# SCH_7segment.net
KiCad netlist of a schematic drawn in EasyEDA
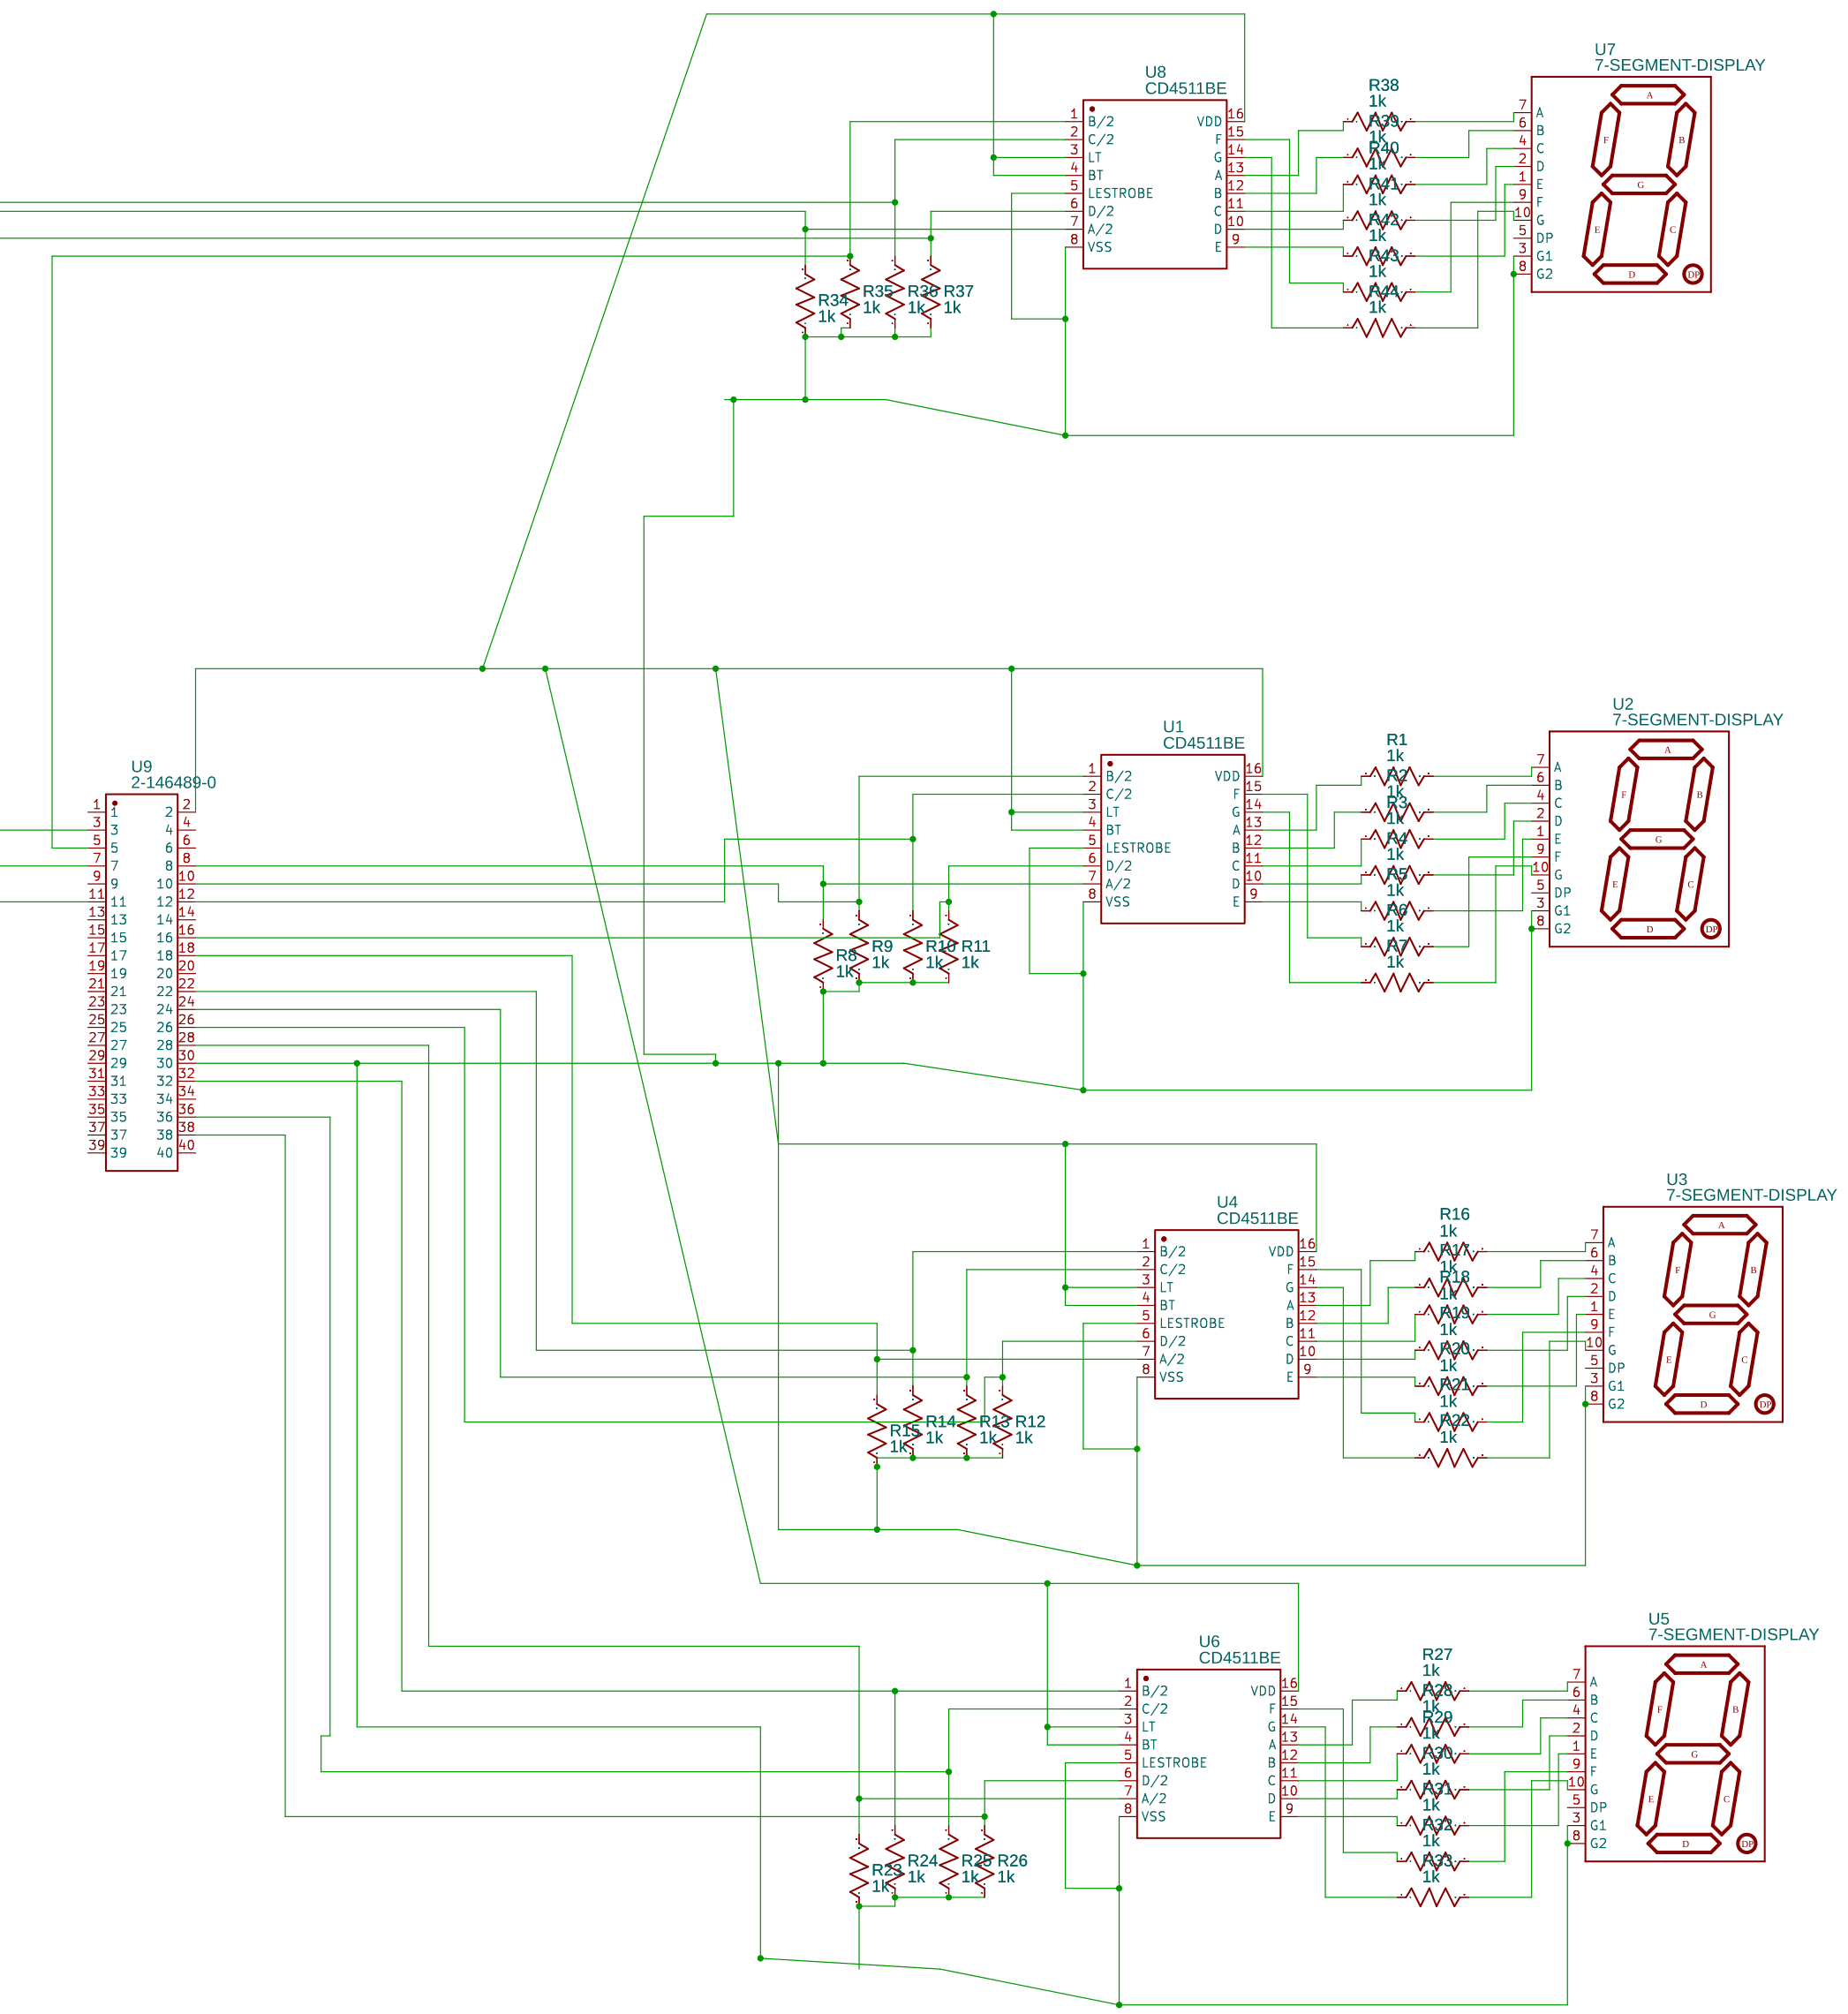
[diagram p0: schematic sheet]

(export (version "E")
  (design (tool "Eeschema 10.0.6"))
  (components
    (comp (ref "R1") (value "1k") (libsource (lib "") (part "R_AXIAL-0.4_US")))
    (comp (ref "R2") (value "1k") (libsource (lib "") (part "R_AXIAL-0.4_US")))
    (comp (ref "R3") (value "1k") (libsource (lib "") (part "R_AXIAL-0.4_US")))
    (comp (ref "R4") (value "1k") (libsource (lib "") (part "R_AXIAL-0.4_US")))
    (comp (ref "R5") (value "1k") (libsource (lib "") (part "R_AXIAL-0.4_US")))
    (comp (ref "R6") (value "1k") (libsource (lib "") (part "R_AXIAL-0.4_US")))
    (comp (ref "R7") (value "1k") (libsource (lib "") (part "R_AXIAL-0.4_US")))
    (comp (ref "R8") (value "1k") (libsource (lib "") (part "R_AXIAL-0.4_US_1")))
    (comp (ref "R9") (value "1k") (libsource (lib "") (part "R_AXIAL-0.4_US_1")))
    (comp (ref "R10") (value "1k") (libsource (lib "") (part "R_AXIAL-0.4_US_1")))
    (comp (ref "R11") (value "1k") (libsource (lib "") (part "R_AXIAL-0.4_US_1")))
    (comp (ref "R12") (value "1k") (libsource (lib "") (part "R_AXIAL-0.4_US_1")))
    (comp (ref "R13") (value "1k") (libsource (lib "") (part "R_AXIAL-0.4_US_1")))
    (comp (ref "R14") (value "1k") (libsource (lib "") (part "R_AXIAL-0.4_US_1")))
    (comp (ref "R15") (value "1k") (libsource (lib "") (part "R_AXIAL-0.4_US_1")))
    (comp (ref "R16") (value "1k") (libsource (lib "") (part "R_AXIAL-0.4_US")))
    (comp (ref "R17") (value "1k") (libsource (lib "") (part "R_AXIAL-0.4_US")))
    (comp (ref "R18") (value "1k") (libsource (lib "") (part "R_AXIAL-0.4_US")))
    (comp (ref "R19") (value "1k") (libsource (lib "") (part "R_AXIAL-0.4_US")))
    (comp (ref "R20") (value "1k") (libsource (lib "") (part "R_AXIAL-0.4_US")))
    (comp (ref "R21") (value "1k") (libsource (lib "") (part "R_AXIAL-0.4_US")))
    (comp (ref "R22") (value "1k") (libsource (lib "") (part "R_AXIAL-0.4_US")))
    (comp (ref "R23") (value "1k") (libsource (lib "") (part "R_AXIAL-0.4_US_1")))
    (comp (ref "R24") (value "1k") (libsource (lib "") (part "R_AXIAL-0.4_US_1")))
    (comp (ref "R25") (value "1k") (libsource (lib "") (part "R_AXIAL-0.4_US_1")))
    (comp (ref "R26") (value "1k") (libsource (lib "") (part "R_AXIAL-0.4_US_1")))
    (comp (ref "R27") (value "1k") (libsource (lib "") (part "R_AXIAL-0.4_US")))
    (comp (ref "R28") (value "1k") (libsource (lib "") (part "R_AXIAL-0.4_US")))
    (comp (ref "R29") (value "1k") (libsource (lib "") (part "R_AXIAL-0.4_US")))
    (comp (ref "R30") (value "1k") (libsource (lib "") (part "R_AXIAL-0.4_US")))
    (comp (ref "R31") (value "1k") (libsource (lib "") (part "R_AXIAL-0.4_US")))
    (comp (ref "R32") (value "1k") (libsource (lib "") (part "R_AXIAL-0.4_US")))
    (comp (ref "R33") (value "1k") (libsource (lib "") (part "R_AXIAL-0.4_US")))
    (comp (ref "R34") (value "1k") (libsource (lib "") (part "R_AXIAL-0.4_US_1")))
    (comp (ref "R35") (value "1k") (libsource (lib "") (part "R_AXIAL-0.4_US_1")))
    (comp (ref "R36") (value "1k") (libsource (lib "") (part "R_AXIAL-0.4_US_1")))
    (comp (ref "R37") (value "1k") (libsource (lib "") (part "R_AXIAL-0.4_US_1")))
    (comp (ref "R38") (value "1k") (libsource (lib "") (part "R_AXIAL-0.4_US")))
    (comp (ref "R39") (value "1k") (libsource (lib "") (part "R_AXIAL-0.4_US")))
    (comp (ref "R40") (value "1k") (libsource (lib "") (part "R_AXIAL-0.4_US")))
    (comp (ref "R41") (value "1k") (libsource (lib "") (part "R_AXIAL-0.4_US")))
    (comp (ref "R42") (value "1k") (libsource (lib "") (part "R_AXIAL-0.4_US")))
    (comp (ref "R43") (value "1k") (libsource (lib "") (part "R_AXIAL-0.4_US")))
    (comp (ref "R44") (value "1k") (libsource (lib "") (part "R_AXIAL-0.4_US")))
    (comp (ref "U1")
      (value "CD4511BE")
      (fields (field (name "BOM_Supplier Part") "C5327"))
      (libsource (lib "") (part "CD4511BE"))
    )
    (comp (ref "U2") (value "7-SEGMENT-DISPLAY") (libsource (lib "") (part "7-SEGMENT-DISPLAY")))
    (comp (ref "U3") (value "7-SEGMENT-DISPLAY") (libsource (lib "") (part "7-SEGMENT-DISPLAY")))
    (comp (ref "U4")
      (value "CD4511BE")
      (fields (field (name "BOM_Supplier Part") "C5327"))
      (libsource (lib "") (part "CD4511BE"))
    )
    (comp (ref "U5") (value "7-SEGMENT-DISPLAY") (libsource (lib "") (part "7-SEGMENT-DISPLAY")))
    (comp (ref "U6")
      (value "CD4511BE")
      (fields (field (name "BOM_Supplier Part") "C5327"))
      (libsource (lib "") (part "CD4511BE"))
    )
    (comp (ref "U7") (value "7-SEGMENT-DISPLAY") (libsource (lib "") (part "7-SEGMENT-DISPLAY")))
    (comp (ref "U8")
      (value "CD4511BE")
      (fields (field (name "BOM_Supplier Part") "C5327"))
      (libsource (lib "") (part "CD4511BE"))
    )
    (comp (ref "U9")
      (value "2-146489-0")
      (fields (field (name "BOM_Supplier Part") "C3334839"))
      (libsource (lib "") (part "2-146489-0"))
    )
  )
  (nets
    (net (code "1") (name "Net-(R23-Pad1)") (class "Default")
      (node (ref "R23") (pin "1") (pinfunction "1_1") (pintype "unspecified"))
      (node (ref "R24") (pin "1") (pinfunction "1_1") (pintype "unspecified"))
      (node (ref "R25") (pin "1") (pinfunction "1_1") (pintype "unspecified"))
      (node (ref "R26") (pin "1") (pinfunction "1_1") (pintype "unspecified"))
    )
    (net (code "2") (name "Net-(U1-A)") (class "Default")
      (node (ref "R1") (pin "1") (pinfunction "1_1") (pintype "unspecified"))
      (node (ref "U1") (pin "13") (pinfunction "A_13") (pintype "unspecified"))
    )
    (net (code "3") (name "Net-(U1-A{slash}2)") (class "Default")
      (node (ref "R8") (pin "2") (pinfunction "2_2") (pintype "unspecified"))
      (node (ref "U1") (pin "7") (pinfunction "A/2_7") (pintype "unspecified"))
      (node (ref "U9") (pin "8") (pinfunction "8_8") (pintype "unspecified"))
    )
    (net (code "4") (name "Net-(U1-B)") (class "Default")
      (node (ref "R2") (pin "1") (pinfunction "1_1") (pintype "unspecified"))
      (node (ref "U1") (pin "12") (pinfunction "B_12") (pintype "unspecified"))
    )
    (net (code "5") (name "Net-(U1-BT)") (class "Default")
      (node (ref "U1") (pin "16") (pinfunction "VDD_16") (pintype "unspecified"))
      (node (ref "U1") (pin "3") (pinfunction "LT_3") (pintype "unspecified"))
      (node (ref "U1") (pin "4") (pinfunction "BT_4") (pintype "unspecified"))
      (node (ref "U4") (pin "16") (pinfunction "VDD_16") (pintype "unspecified"))
      (node (ref "U4") (pin "3") (pinfunction "LT_3") (pintype "unspecified"))
      (node (ref "U4") (pin "4") (pinfunction "BT_4") (pintype "unspecified"))
      (node (ref "U6") (pin "16") (pinfunction "VDD_16") (pintype "unspecified"))
      (node (ref "U6") (pin "3") (pinfunction "LT_3") (pintype "unspecified"))
      (node (ref "U6") (pin "4") (pinfunction "BT_4") (pintype "unspecified"))
      (node (ref "U8") (pin "16") (pinfunction "VDD_16") (pintype "unspecified"))
      (node (ref "U8") (pin "3") (pinfunction "LT_3") (pintype "unspecified"))
      (node (ref "U8") (pin "4") (pinfunction "BT_4") (pintype "unspecified"))
      (node (ref "U9") (pin "2") (pinfunction "2_2") (pintype "unspecified"))
    )
    (net (code "6") (name "Net-(U1-B{slash}2)") (class "Default")
      (node (ref "R9") (pin "2") (pinfunction "2_2") (pintype "unspecified"))
      (node (ref "U1") (pin "1") (pinfunction "B/2_1") (pintype "unspecified"))
      (node (ref "U9") (pin "10") (pinfunction "10_10") (pintype "unspecified"))
    )
    (net (code "7") (name "Net-(U1-C)") (class "Default")
      (node (ref "R3") (pin "1") (pinfunction "1_1") (pintype "unspecified"))
      (node (ref "U1") (pin "11") (pinfunction "C_11") (pintype "unspecified"))
    )
    (net (code "8") (name "Net-(U1-C{slash}2)") (class "Default")
      (node (ref "R10") (pin "2") (pinfunction "2_2") (pintype "unspecified"))
      (node (ref "U1") (pin "2") (pinfunction "C/2_2") (pintype "unspecified"))
      (node (ref "U9") (pin "12") (pinfunction "12_12") (pintype "unspecified"))
    )
    (net (code "9") (name "Net-(U1-D)") (class "Default")
      (node (ref "R4") (pin "1") (pinfunction "1_1") (pintype "unspecified"))
      (node (ref "U1") (pin "10") (pinfunction "D_10") (pintype "unspecified"))
    )
    (net (code "10") (name "Net-(U1-D{slash}2)") (class "Default")
      (node (ref "R11") (pin "2") (pinfunction "2_2") (pintype "unspecified"))
      (node (ref "U1") (pin "6") (pinfunction "D/2_6") (pintype "unspecified"))
      (node (ref "U9") (pin "16") (pinfunction "16_16") (pintype "unspecified"))
    )
    (net (code "11") (name "Net-(U1-E)") (class "Default")
      (node (ref "R5") (pin "1") (pinfunction "1_1") (pintype "unspecified"))
      (node (ref "U1") (pin "9") (pinfunction "E_9") (pintype "unspecified"))
    )
    (net (code "12") (name "Net-(U1-F)") (class "Default")
      (node (ref "R6") (pin "1") (pinfunction "1_1") (pintype "unspecified"))
      (node (ref "U1") (pin "15") (pinfunction "F_15") (pintype "unspecified"))
    )
    (net (code "13") (name "Net-(U1-G)") (class "Default")
      (node (ref "R7") (pin "1") (pinfunction "1_1") (pintype "unspecified"))
      (node (ref "U1") (pin "14") (pinfunction "G_14") (pintype "unspecified"))
    )
    (net (code "14") (name "Net-(U1-LESTROBE)") (class "Default")
      (node (ref "R10") (pin "1") (pinfunction "1_1") (pintype "unspecified"))
      (node (ref "R11") (pin "1") (pinfunction "1_1") (pintype "unspecified"))
      (node (ref "R12") (pin "1") (pinfunction "1_1") (pintype "unspecified"))
      (node (ref "R13") (pin "1") (pinfunction "1_1") (pintype "unspecified"))
      (node (ref "R14") (pin "1") (pinfunction "1_1") (pintype "unspecified"))
      (node (ref "R15") (pin "1") (pinfunction "1_1") (pintype "unspecified"))
      (node (ref "R34") (pin "1") (pinfunction "1_1") (pintype "unspecified"))
      (node (ref "R35") (pin "1") (pinfunction "1_1") (pintype "unspecified"))
      (node (ref "R36") (pin "1") (pinfunction "1_1") (pintype "unspecified"))
      (node (ref "R37") (pin "1") (pinfunction "1_1") (pintype "unspecified"))
      (node (ref "R8") (pin "1") (pinfunction "1_1") (pintype "unspecified"))
      (node (ref "R9") (pin "1") (pinfunction "1_1") (pintype "unspecified"))
      (node (ref "U1") (pin "5") (pinfunction "LESTROBE_5") (pintype "unspecified"))
      (node (ref "U1") (pin "8") (pinfunction "VSS_8") (pintype "unspecified"))
      (node (ref "U2") (pin "3") (pinfunction "G1_3") (pintype "unspecified"))
      (node (ref "U2") (pin "8") (pinfunction "G2_8") (pintype "unspecified"))
      (node (ref "U3") (pin "3") (pinfunction "G1_3") (pintype "unspecified"))
      (node (ref "U3") (pin "8") (pinfunction "G2_8") (pintype "unspecified"))
      (node (ref "U4") (pin "5") (pinfunction "LESTROBE_5") (pintype "unspecified"))
      (node (ref "U4") (pin "8") (pinfunction "VSS_8") (pintype "unspecified"))
      (node (ref "U5") (pin "3") (pinfunction "G1_3") (pintype "unspecified"))
      (node (ref "U5") (pin "8") (pinfunction "G2_8") (pintype "unspecified"))
      (node (ref "U6") (pin "5") (pinfunction "LESTROBE_5") (pintype "unspecified"))
      (node (ref "U6") (pin "8") (pinfunction "VSS_8") (pintype "unspecified"))
      (node (ref "U7") (pin "3") (pinfunction "G1_3") (pintype "unspecified"))
      (node (ref "U7") (pin "8") (pinfunction "G2_8") (pintype "unspecified"))
      (node (ref "U8") (pin "5") (pinfunction "LESTROBE_5") (pintype "unspecified"))
      (node (ref "U8") (pin "8") (pinfunction "VSS_8") (pintype "unspecified"))
      (node (ref "U9") (pin "30") (pinfunction "30_30") (pintype "unspecified"))
    )
    (net (code "15") (name "Net-(U2-A)") (class "Default")
      (node (ref "R1") (pin "2") (pinfunction "2_2") (pintype "unspecified"))
      (node (ref "U2") (pin "7") (pinfunction "A_7") (pintype "unspecified"))
    )
    (net (code "16") (name "Net-(U2-B)") (class "Default")
      (node (ref "R2") (pin "2") (pinfunction "2_2") (pintype "unspecified"))
      (node (ref "U2") (pin "6") (pinfunction "B_6") (pintype "unspecified"))
    )
    (net (code "17") (name "Net-(U2-C)") (class "Default")
      (node (ref "R3") (pin "2") (pinfunction "2_2") (pintype "unspecified"))
      (node (ref "U2") (pin "4") (pinfunction "C_4") (pintype "unspecified"))
    )
    (net (code "18") (name "Net-(U2-D)") (class "Default")
      (node (ref "R4") (pin "2") (pinfunction "2_2") (pintype "unspecified"))
      (node (ref "U2") (pin "2") (pinfunction "D_2") (pintype "unspecified"))
    )
    (net (code "19") (name "Net-(U2-E)") (class "Default")
      (node (ref "R5") (pin "2") (pinfunction "2_2") (pintype "unspecified"))
      (node (ref "U2") (pin "1") (pinfunction "E_1") (pintype "unspecified"))
    )
    (net (code "20") (name "Net-(U2-F)") (class "Default")
      (node (ref "R6") (pin "2") (pinfunction "2_2") (pintype "unspecified"))
      (node (ref "U2") (pin "9") (pinfunction "F_9") (pintype "unspecified"))
    )
    (net (code "21") (name "Net-(U2-G)") (class "Default")
      (node (ref "R7") (pin "2") (pinfunction "2_2") (pintype "unspecified"))
      (node (ref "U2") (pin "10") (pinfunction "G_10") (pintype "unspecified"))
    )
    (net (code "22") (name "Net-(U3-A)") (class "Default")
      (node (ref "R16") (pin "2") (pinfunction "2_2") (pintype "unspecified"))
      (node (ref "U3") (pin "7") (pinfunction "A_7") (pintype "unspecified"))
    )
    (net (code "23") (name "Net-(U3-B)") (class "Default")
      (node (ref "R17") (pin "2") (pinfunction "2_2") (pintype "unspecified"))
      (node (ref "U3") (pin "6") (pinfunction "B_6") (pintype "unspecified"))
    )
    (net (code "24") (name "Net-(U3-C)") (class "Default")
      (node (ref "R18") (pin "2") (pinfunction "2_2") (pintype "unspecified"))
      (node (ref "U3") (pin "4") (pinfunction "C_4") (pintype "unspecified"))
    )
    (net (code "25") (name "Net-(U3-D)") (class "Default")
      (node (ref "R19") (pin "2") (pinfunction "2_2") (pintype "unspecified"))
      (node (ref "U3") (pin "2") (pinfunction "D_2") (pintype "unspecified"))
    )
    (net (code "26") (name "Net-(U3-E)") (class "Default")
      (node (ref "R20") (pin "2") (pinfunction "2_2") (pintype "unspecified"))
      (node (ref "U3") (pin "1") (pinfunction "E_1") (pintype "unspecified"))
    )
    (net (code "27") (name "Net-(U3-F)") (class "Default")
      (node (ref "R21") (pin "2") (pinfunction "2_2") (pintype "unspecified"))
      (node (ref "U3") (pin "9") (pinfunction "F_9") (pintype "unspecified"))
    )
    (net (code "28") (name "Net-(U3-G)") (class "Default")
      (node (ref "R22") (pin "2") (pinfunction "2_2") (pintype "unspecified"))
      (node (ref "U3") (pin "10") (pinfunction "G_10") (pintype "unspecified"))
    )
    (net (code "29") (name "Net-(U4-A)") (class "Default")
      (node (ref "R16") (pin "1") (pinfunction "1_1") (pintype "unspecified"))
      (node (ref "U4") (pin "13") (pinfunction "A_13") (pintype "unspecified"))
    )
    (net (code "30") (name "Net-(U4-A{slash}2)") (class "Default")
      (node (ref "R15") (pin "2") (pinfunction "2_2") (pintype "unspecified"))
      (node (ref "U4") (pin "7") (pinfunction "A/2_7") (pintype "unspecified"))
      (node (ref "U9") (pin "18") (pinfunction "18_18") (pintype "unspecified"))
    )
    (net (code "31") (name "Net-(U4-B)") (class "Default")
      (node (ref "R17") (pin "1") (pinfunction "1_1") (pintype "unspecified"))
      (node (ref "U4") (pin "12") (pinfunction "B_12") (pintype "unspecified"))
    )
    (net (code "32") (name "Net-(U4-B{slash}2)") (class "Default")
      (node (ref "R14") (pin "2") (pinfunction "2_2") (pintype "unspecified"))
      (node (ref "U4") (pin "1") (pinfunction "B/2_1") (pintype "unspecified"))
      (node (ref "U9") (pin "22") (pinfunction "22_22") (pintype "unspecified"))
    )
    (net (code "33") (name "Net-(U4-C)") (class "Default")
      (node (ref "R18") (pin "1") (pinfunction "1_1") (pintype "unspecified"))
      (node (ref "U4") (pin "11") (pinfunction "C_11") (pintype "unspecified"))
    )
    (net (code "34") (name "Net-(U4-C{slash}2)") (class "Default")
      (node (ref "R13") (pin "2") (pinfunction "2_2") (pintype "unspecified"))
      (node (ref "U4") (pin "2") (pinfunction "C/2_2") (pintype "unspecified"))
      (node (ref "U9") (pin "24") (pinfunction "24_24") (pintype "unspecified"))
    )
    (net (code "35") (name "Net-(U4-D)") (class "Default")
      (node (ref "R19") (pin "1") (pinfunction "1_1") (pintype "unspecified"))
      (node (ref "U4") (pin "10") (pinfunction "D_10") (pintype "unspecified"))
    )
    (net (code "36") (name "Net-(U4-D{slash}2)") (class "Default")
      (node (ref "R12") (pin "2") (pinfunction "2_2") (pintype "unspecified"))
      (node (ref "U4") (pin "6") (pinfunction "D/2_6") (pintype "unspecified"))
      (node (ref "U9") (pin "26") (pinfunction "26_26") (pintype "unspecified"))
    )
    (net (code "37") (name "Net-(U4-E)") (class "Default")
      (node (ref "R20") (pin "1") (pinfunction "1_1") (pintype "unspecified"))
      (node (ref "U4") (pin "9") (pinfunction "E_9") (pintype "unspecified"))
    )
    (net (code "38") (name "Net-(U4-F)") (class "Default")
      (node (ref "R21") (pin "1") (pinfunction "1_1") (pintype "unspecified"))
      (node (ref "U4") (pin "15") (pinfunction "F_15") (pintype "unspecified"))
    )
    (net (code "39") (name "Net-(U4-G)") (class "Default")
      (node (ref "R22") (pin "1") (pinfunction "1_1") (pintype "unspecified"))
      (node (ref "U4") (pin "14") (pinfunction "G_14") (pintype "unspecified"))
    )
    (net (code "40") (name "Net-(U5-A)") (class "Default")
      (node (ref "R27") (pin "2") (pinfunction "2_2") (pintype "unspecified"))
      (node (ref "U5") (pin "7") (pinfunction "A_7") (pintype "unspecified"))
    )
    (net (code "41") (name "Net-(U5-B)") (class "Default")
      (node (ref "R28") (pin "2") (pinfunction "2_2") (pintype "unspecified"))
      (node (ref "U5") (pin "6") (pinfunction "B_6") (pintype "unspecified"))
    )
    (net (code "42") (name "Net-(U5-C)") (class "Default")
      (node (ref "R29") (pin "2") (pinfunction "2_2") (pintype "unspecified"))
      (node (ref "U5") (pin "4") (pinfunction "C_4") (pintype "unspecified"))
    )
    (net (code "43") (name "Net-(U5-D)") (class "Default")
      (node (ref "R30") (pin "2") (pinfunction "2_2") (pintype "unspecified"))
      (node (ref "U5") (pin "2") (pinfunction "D_2") (pintype "unspecified"))
    )
    (net (code "44") (name "Net-(U5-E)") (class "Default")
      (node (ref "R31") (pin "2") (pinfunction "2_2") (pintype "unspecified"))
      (node (ref "U5") (pin "1") (pinfunction "E_1") (pintype "unspecified"))
    )
    (net (code "45") (name "Net-(U5-F)") (class "Default")
      (node (ref "R32") (pin "2") (pinfunction "2_2") (pintype "unspecified"))
      (node (ref "U5") (pin "9") (pinfunction "F_9") (pintype "unspecified"))
    )
    (net (code "46") (name "Net-(U5-G)") (class "Default")
      (node (ref "R33") (pin "2") (pinfunction "2_2") (pintype "unspecified"))
      (node (ref "U5") (pin "10") (pinfunction "G_10") (pintype "unspecified"))
    )
    (net (code "47") (name "Net-(U6-A)") (class "Default")
      (node (ref "R27") (pin "1") (pinfunction "1_1") (pintype "unspecified"))
      (node (ref "U6") (pin "13") (pinfunction "A_13") (pintype "unspecified"))
    )
    (net (code "48") (name "Net-(U6-A{slash}2)") (class "Default")
      (node (ref "R23") (pin "2") (pinfunction "2_2") (pintype "unspecified"))
      (node (ref "U6") (pin "7") (pinfunction "A/2_7") (pintype "unspecified"))
      (node (ref "U9") (pin "28") (pinfunction "28_28") (pintype "unspecified"))
    )
    (net (code "49") (name "Net-(U6-B)") (class "Default")
      (node (ref "R28") (pin "1") (pinfunction "1_1") (pintype "unspecified"))
      (node (ref "U6") (pin "12") (pinfunction "B_12") (pintype "unspecified"))
    )
    (net (code "50") (name "Net-(U6-B{slash}2)") (class "Default")
      (node (ref "R24") (pin "2") (pinfunction "2_2") (pintype "unspecified"))
      (node (ref "U6") (pin "1") (pinfunction "B/2_1") (pintype "unspecified"))
      (node (ref "U9") (pin "32") (pinfunction "32_32") (pintype "unspecified"))
    )
    (net (code "51") (name "Net-(U6-C)") (class "Default")
      (node (ref "R29") (pin "1") (pinfunction "1_1") (pintype "unspecified"))
      (node (ref "U6") (pin "11") (pinfunction "C_11") (pintype "unspecified"))
    )
    (net (code "52") (name "Net-(U6-C{slash}2)") (class "Default")
      (node (ref "R25") (pin "2") (pinfunction "2_2") (pintype "unspecified"))
      (node (ref "U6") (pin "2") (pinfunction "C/2_2") (pintype "unspecified"))
      (node (ref "U9") (pin "36") (pinfunction "36_36") (pintype "unspecified"))
    )
    (net (code "53") (name "Net-(U6-D)") (class "Default")
      (node (ref "R30") (pin "1") (pinfunction "1_1") (pintype "unspecified"))
      (node (ref "U6") (pin "10") (pinfunction "D_10") (pintype "unspecified"))
    )
    (net (code "54") (name "Net-(U6-D{slash}2)") (class "Default")
      (node (ref "R26") (pin "2") (pinfunction "2_2") (pintype "unspecified"))
      (node (ref "U6") (pin "6") (pinfunction "D/2_6") (pintype "unspecified"))
      (node (ref "U9") (pin "38") (pinfunction "38_38") (pintype "unspecified"))
    )
    (net (code "55") (name "Net-(U6-E)") (class "Default")
      (node (ref "R31") (pin "1") (pinfunction "1_1") (pintype "unspecified"))
      (node (ref "U6") (pin "9") (pinfunction "E_9") (pintype "unspecified"))
    )
    (net (code "56") (name "Net-(U6-F)") (class "Default")
      (node (ref "R32") (pin "1") (pinfunction "1_1") (pintype "unspecified"))
      (node (ref "U6") (pin "15") (pinfunction "F_15") (pintype "unspecified"))
    )
    (net (code "57") (name "Net-(U6-G)") (class "Default")
      (node (ref "R33") (pin "1") (pinfunction "1_1") (pintype "unspecified"))
      (node (ref "U6") (pin "14") (pinfunction "G_14") (pintype "unspecified"))
    )
    (net (code "58") (name "Net-(U7-A)") (class "Default")
      (node (ref "R38") (pin "2") (pinfunction "2_2") (pintype "unspecified"))
      (node (ref "U7") (pin "7") (pinfunction "A_7") (pintype "unspecified"))
    )
    (net (code "59") (name "Net-(U7-B)") (class "Default")
      (node (ref "R39") (pin "2") (pinfunction "2_2") (pintype "unspecified"))
      (node (ref "U7") (pin "6") (pinfunction "B_6") (pintype "unspecified"))
    )
    (net (code "60") (name "Net-(U7-C)") (class "Default")
      (node (ref "R40") (pin "2") (pinfunction "2_2") (pintype "unspecified"))
      (node (ref "U7") (pin "4") (pinfunction "C_4") (pintype "unspecified"))
    )
    (net (code "61") (name "Net-(U7-D)") (class "Default")
      (node (ref "R41") (pin "2") (pinfunction "2_2") (pintype "unspecified"))
      (node (ref "U7") (pin "2") (pinfunction "D_2") (pintype "unspecified"))
    )
    (net (code "62") (name "Net-(U7-E)") (class "Default")
      (node (ref "R42") (pin "2") (pinfunction "2_2") (pintype "unspecified"))
      (node (ref "U7") (pin "1") (pinfunction "E_1") (pintype "unspecified"))
    )
    (net (code "63") (name "Net-(U7-F)") (class "Default")
      (node (ref "R43") (pin "2") (pinfunction "2_2") (pintype "unspecified"))
      (node (ref "U7") (pin "9") (pinfunction "F_9") (pintype "unspecified"))
    )
    (net (code "64") (name "Net-(U7-G)") (class "Default")
      (node (ref "R44") (pin "2") (pinfunction "2_2") (pintype "unspecified"))
      (node (ref "U7") (pin "10") (pinfunction "G_10") (pintype "unspecified"))
    )
    (net (code "65") (name "Net-(U8-A)") (class "Default")
      (node (ref "R38") (pin "1") (pinfunction "1_1") (pintype "unspecified"))
      (node (ref "U8") (pin "13") (pinfunction "A_13") (pintype "unspecified"))
    )
    (net (code "66") (name "Net-(U8-A{slash}2)") (class "Default")
      (node (ref "R34") (pin "2") (pinfunction "2_2") (pintype "unspecified"))
      (node (ref "U8") (pin "7") (pinfunction "A/2_7") (pintype "unspecified"))
      (node (ref "U9") (pin "3") (pinfunction "3_3") (pintype "unspecified"))
    )
    (net (code "67") (name "Net-(U8-B)") (class "Default")
      (node (ref "R39") (pin "1") (pinfunction "1_1") (pintype "unspecified"))
      (node (ref "U8") (pin "12") (pinfunction "B_12") (pintype "unspecified"))
    )
    (net (code "68") (name "Net-(U8-B{slash}2)") (class "Default")
      (node (ref "R35") (pin "2") (pinfunction "2_2") (pintype "unspecified"))
      (node (ref "U8") (pin "1") (pinfunction "B/2_1") (pintype "unspecified"))
      (node (ref "U9") (pin "5") (pinfunction "5_5") (pintype "unspecified"))
    )
    (net (code "69") (name "Net-(U8-C)") (class "Default")
      (node (ref "R40") (pin "1") (pinfunction "1_1") (pintype "unspecified"))
      (node (ref "U8") (pin "11") (pinfunction "C_11") (pintype "unspecified"))
    )
    (net (code "70") (name "Net-(U8-C{slash}2)") (class "Default")
      (node (ref "R36") (pin "2") (pinfunction "2_2") (pintype "unspecified"))
      (node (ref "U8") (pin "2") (pinfunction "C/2_2") (pintype "unspecified"))
      (node (ref "U9") (pin "7") (pinfunction "7_7") (pintype "unspecified"))
    )
    (net (code "71") (name "Net-(U8-D)") (class "Default")
      (node (ref "R41") (pin "1") (pinfunction "1_1") (pintype "unspecified"))
      (node (ref "U8") (pin "10") (pinfunction "D_10") (pintype "unspecified"))
    )
    (net (code "72") (name "Net-(U8-D{slash}2)") (class "Default")
      (node (ref "R37") (pin "2") (pinfunction "2_2") (pintype "unspecified"))
      (node (ref "U8") (pin "6") (pinfunction "D/2_6") (pintype "unspecified"))
      (node (ref "U9") (pin "11") (pinfunction "11_11") (pintype "unspecified"))
    )
    (net (code "73") (name "Net-(U8-E)") (class "Default")
      (node (ref "R42") (pin "1") (pinfunction "1_1") (pintype "unspecified"))
      (node (ref "U8") (pin "9") (pinfunction "E_9") (pintype "unspecified"))
    )
    (net (code "74") (name "Net-(U8-F)") (class "Default")
      (node (ref "R43") (pin "1") (pinfunction "1_1") (pintype "unspecified"))
      (node (ref "U8") (pin "15") (pinfunction "F_15") (pintype "unspecified"))
    )
    (net (code "75") (name "Net-(U8-G)") (class "Default")
      (node (ref "R44") (pin "1") (pinfunction "1_1") (pintype "unspecified"))
      (node (ref "U8") (pin "14") (pinfunction "G_14") (pintype "unspecified"))
    )
    (net (code "76") (name "unconnected-(U2-DP-Pad5)") (class "Default")
      (node (ref "U2") (pin "5") (pinfunction "DP_5") (pintype "unspecified"))
    )
    (net (code "77") (name "unconnected-(U3-DP-Pad5)") (class "Default")
      (node (ref "U3") (pin "5") (pinfunction "DP_5") (pintype "unspecified"))
    )
    (net (code "78") (name "unconnected-(U5-DP-Pad5)") (class "Default")
      (node (ref "U5") (pin "5") (pinfunction "DP_5") (pintype "unspecified"))
    )
    (net (code "79") (name "unconnected-(U7-DP-Pad5)") (class "Default")
      (node (ref "U7") (pin "5") (pinfunction "DP_5") (pintype "unspecified"))
    )
    (net (code "80") (name "unconnected-(U9-Pad1)") (class "Default")
      (node (ref "U9") (pin "1") (pinfunction "1_1") (pintype "unspecified"))
    )
    (net (code "81") (name "unconnected-(U9-Pad4)") (class "Default")
      (node (ref "U9") (pin "4") (pinfunction "4_4") (pintype "unspecified"))
    )
    (net (code "82") (name "unconnected-(U9-Pad6)") (class "Default")
      (node (ref "U9") (pin "6") (pinfunction "6_6") (pintype "unspecified"))
    )
    (net (code "83") (name "unconnected-(U9-Pad9)") (class "Default")
      (node (ref "U9") (pin "9") (pinfunction "9_9") (pintype "unspecified"))
    )
    (net (code "84") (name "unconnected-(U9-Pad13)") (class "Default")
      (node (ref "U9") (pin "13") (pinfunction "13_13") (pintype "unspecified"))
    )
    (net (code "85") (name "unconnected-(U9-Pad14)") (class "Default")
      (node (ref "U9") (pin "14") (pinfunction "14_14") (pintype "unspecified"))
    )
    (net (code "86") (name "unconnected-(U9-Pad15)") (class "Default")
      (node (ref "U9") (pin "15") (pinfunction "15_15") (pintype "unspecified"))
    )
    (net (code "87") (name "unconnected-(U9-Pad17)") (class "Default")
      (node (ref "U9") (pin "17") (pinfunction "17_17") (pintype "unspecified"))
    )
    (net (code "88") (name "unconnected-(U9-Pad19)") (class "Default")
      (node (ref "U9") (pin "19") (pinfunction "19_19") (pintype "unspecified"))
    )
    (net (code "89") (name "unconnected-(U9-Pad20)") (class "Default")
      (node (ref "U9") (pin "20") (pinfunction "20_20") (pintype "unspecified"))
    )
    (net (code "90") (name "unconnected-(U9-Pad21)") (class "Default")
      (node (ref "U9") (pin "21") (pinfunction "21_21") (pintype "unspecified"))
    )
    (net (code "91") (name "unconnected-(U9-Pad23)") (class "Default")
      (node (ref "U9") (pin "23") (pinfunction "23_23") (pintype "unspecified"))
    )
    (net (code "92") (name "unconnected-(U9-Pad25)") (class "Default")
      (node (ref "U9") (pin "25") (pinfunction "25_25") (pintype "unspecified"))
    )
    (net (code "93") (name "unconnected-(U9-Pad27)") (class "Default")
      (node (ref "U9") (pin "27") (pinfunction "27_27") (pintype "unspecified"))
    )
    (net (code "94") (name "unconnected-(U9-Pad29)") (class "Default")
      (node (ref "U9") (pin "29") (pinfunction "29_29") (pintype "unspecified"))
    )
    (net (code "95") (name "unconnected-(U9-Pad31)") (class "Default")
      (node (ref "U9") (pin "31") (pinfunction "31_31") (pintype "unspecified"))
    )
    (net (code "96") (name "unconnected-(U9-Pad33)") (class "Default")
      (node (ref "U9") (pin "33") (pinfunction "33_33") (pintype "unspecified"))
    )
    (net (code "97") (name "unconnected-(U9-Pad34)") (class "Default")
      (node (ref "U9") (pin "34") (pinfunction "34_34") (pintype "unspecified"))
    )
    (net (code "98") (name "unconnected-(U9-Pad35)") (class "Default")
      (node (ref "U9") (pin "35") (pinfunction "35_35") (pintype "unspecified"))
    )
    (net (code "99") (name "unconnected-(U9-Pad37)") (class "Default")
      (node (ref "U9") (pin "37") (pinfunction "37_37") (pintype "unspecified"))
    )
    (net (code "100") (name "unconnected-(U9-Pad39)") (class "Default")
      (node (ref "U9") (pin "39") (pinfunction "39_39") (pintype "unspecified"))
    )
    (net (code "101") (name "unconnected-(U9-Pad40)") (class "Default")
      (node (ref "U9") (pin "40") (pinfunction "40_40") (pintype "unspecified"))
    )
  )
)
